# Led_Strip_2_colors.net
KiCad netlist of a schematic drawn in Altium Designer
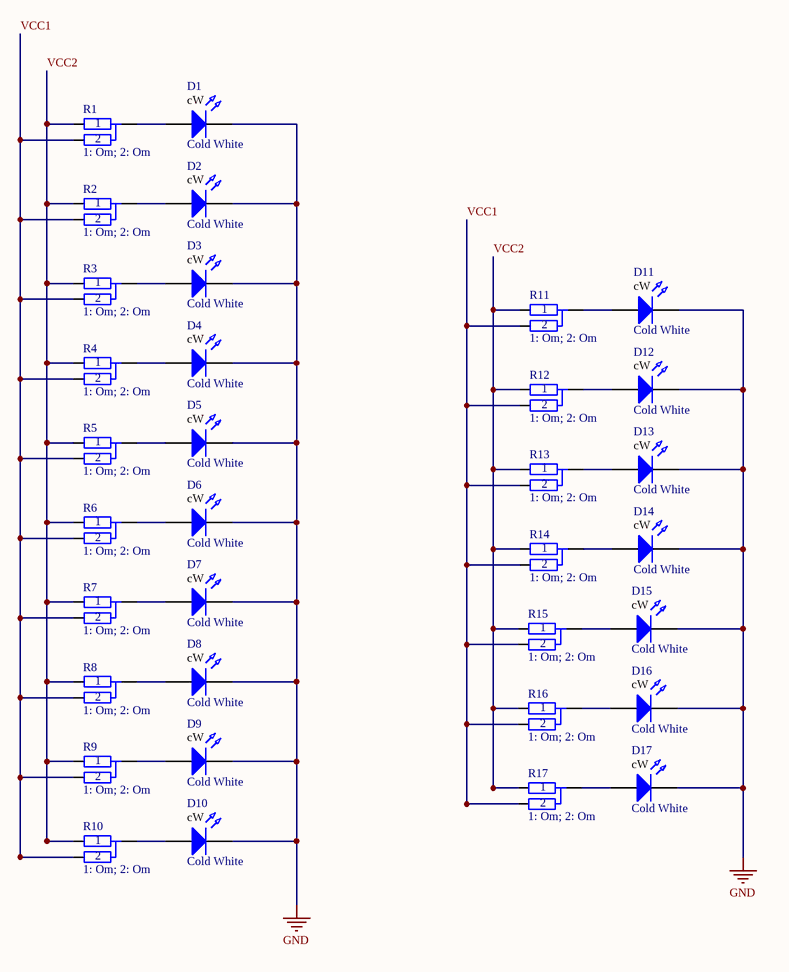
[diagram p0: Led Strip 2 colors.SchDoc]

(export (version "E")
  (design (tool "Eeschema 10.0.6"))
  (components
    (comp (ref "D1")
      (value "Cold White")
      (footprint "LED:LED SMD 5050 White compact R")
      (description "?3v ?20mA")
      (libsource (lib "LED") (part "Led SMD White Cold"))
    )
    (comp (ref "D2")
      (value "Cold White")
      (footprint "LED:LED SMD 5050 White compact R")
      (description "?3v ?20mA")
      (libsource (lib "LED") (part "Led SMD White Cold"))
    )
    (comp (ref "D3")
      (value "Cold White")
      (footprint "LED:LED SMD 5050 White compact R")
      (description "?3v ?20mA")
      (libsource (lib "LED") (part "Led SMD White Cold"))
    )
    (comp (ref "D4")
      (value "Cold White")
      (footprint "LED:LED SMD 5050 White compact R")
      (description "?3v ?20mA")
      (libsource (lib "LED") (part "Led SMD White Cold"))
    )
    (comp (ref "D5")
      (value "Cold White")
      (footprint "LED:LED SMD 5050 White compact R")
      (description "?3v ?20mA")
      (libsource (lib "LED") (part "Led SMD White Cold"))
    )
    (comp (ref "D6")
      (value "Cold White")
      (footprint "LED:LED SMD 5050 White compact R")
      (description "?3v ?20mA")
      (libsource (lib "LED") (part "Led SMD White Cold"))
    )
    (comp (ref "D7")
      (value "Cold White")
      (footprint "LED:LED SMD 5050 White compact R")
      (description "?3v ?20mA")
      (libsource (lib "LED") (part "Led SMD White Cold"))
    )
    (comp (ref "D8")
      (value "Cold White")
      (footprint "LED:LED SMD 5050 White compact R")
      (description "?3v ?20mA")
      (libsource (lib "LED") (part "Led SMD White Cold"))
    )
    (comp (ref "D9")
      (value "Cold White")
      (footprint "LED:LED SMD 5050 White compact R")
      (description "?3v ?20mA")
      (libsource (lib "LED") (part "Led SMD White Cold"))
    )
    (comp (ref "D10")
      (value "Cold White")
      (footprint "LED:LED SMD 5050 White compact R")
      (description "?3v ?20mA")
      (libsource (lib "LED") (part "Led SMD White Cold"))
    )
    (comp (ref "D11")
      (value "Cold White")
      (footprint "LED:LED SMD 5050 White compact R")
      (description "?3v ?20mA")
      (libsource (lib "LED") (part "Led SMD White Cold"))
    )
    (comp (ref "D12")
      (value "Cold White")
      (footprint "LED:LED SMD 5050 White compact R")
      (description "?3v ?20mA")
      (libsource (lib "LED") (part "Led SMD White Cold"))
    )
    (comp (ref "D13")
      (value "Cold White")
      (footprint "LED:LED SMD 5050 White compact R")
      (description "?3v ?20mA")
      (libsource (lib "LED") (part "Led SMD White Cold"))
    )
    (comp (ref "D14")
      (value "Cold White")
      (footprint "LED:LED SMD 5050 White compact R")
      (description "?3v ?20mA")
      (libsource (lib "LED") (part "Led SMD White Cold"))
    )
    (comp (ref "D15")
      (value "Cold White")
      (footprint "LED:LED SMD 5050 White compact R")
      (description "?3v ?20mA")
      (libsource (lib "LED") (part "Led SMD White Cold"))
    )
    (comp (ref "D16")
      (value "Cold White")
      (footprint "LED:LED SMD 5050 White compact R")
      (description "?3v ?20mA")
      (libsource (lib "LED") (part "Led SMD White Cold"))
    )
    (comp (ref "D17")
      (value "Cold White")
      (footprint "LED:LED SMD 5050 White compact R")
      (description "?3v ?20mA")
      (libsource (lib "LED") (part "Led SMD White Cold"))
    )
    (comp (ref "R1")
      (value "1: Om; 2: Om")
      (footprint "PassiveComponents:SMD 0805 (2012) Double")
      (description "Choice from two resistors")
      (libsource (lib "PassiveComponents") (part "Res SMD (Select one way)"))
    )
    (comp (ref "R2")
      (value "1: Om; 2: Om")
      (footprint "PassiveComponents:SMD 0805 (2012) Double")
      (description "Choice from two resistors")
      (libsource (lib "PassiveComponents") (part "Res SMD (Select one way)"))
    )
    (comp (ref "R3")
      (value "1: Om; 2: Om")
      (footprint "PassiveComponents:SMD 0805 (2012) Double")
      (description "Choice from two resistors")
      (libsource (lib "PassiveComponents") (part "Res SMD (Select one way)"))
    )
    (comp (ref "R4")
      (value "1: Om; 2: Om")
      (footprint "PassiveComponents:SMD 0805 (2012) Double")
      (description "Choice from two resistors")
      (libsource (lib "PassiveComponents") (part "Res SMD (Select one way)"))
    )
    (comp (ref "R5")
      (value "1: Om; 2: Om")
      (footprint "PassiveComponents:SMD 0805 (2012) Double")
      (description "Choice from two resistors")
      (libsource (lib "PassiveComponents") (part "Res SMD (Select one way)"))
    )
    (comp (ref "R6")
      (value "1: Om; 2: Om")
      (footprint "PassiveComponents:SMD 0805 (2012) Double")
      (description "Choice from two resistors")
      (libsource (lib "PassiveComponents") (part "Res SMD (Select one way)"))
    )
    (comp (ref "R7")
      (value "1: Om; 2: Om")
      (footprint "PassiveComponents:SMD 0805 (2012) Double")
      (description "Choice from two resistors")
      (libsource (lib "PassiveComponents") (part "Res SMD (Select one way)"))
    )
    (comp (ref "R8")
      (value "1: Om; 2: Om")
      (footprint "PassiveComponents:SMD 0805 (2012) Double")
      (description "Choice from two resistors")
      (libsource (lib "PassiveComponents") (part "Res SMD (Select one way)"))
    )
    (comp (ref "R9")
      (value "1: Om; 2: Om")
      (footprint "PassiveComponents:SMD 0805 (2012) Double")
      (description "Choice from two resistors")
      (libsource (lib "PassiveComponents") (part "Res SMD (Select one way)"))
    )
    (comp (ref "R10")
      (value "1: Om; 2: Om")
      (footprint "PassiveComponents:SMD 0805 (2012) Double")
      (description "Choice from two resistors")
      (libsource (lib "PassiveComponents") (part "Res SMD (Select one way)"))
    )
    (comp (ref "R11")
      (value "1: Om; 2: Om")
      (footprint "PassiveComponents:SMD 0805 (2012) Double")
      (description "Choice from two resistors")
      (libsource (lib "PassiveComponents") (part "Res SMD (Select one way)"))
    )
    (comp (ref "R12")
      (value "1: Om; 2: Om")
      (footprint "PassiveComponents:SMD 0805 (2012) Double")
      (description "Choice from two resistors")
      (libsource (lib "PassiveComponents") (part "Res SMD (Select one way)"))
    )
    (comp (ref "R13")
      (value "1: Om; 2: Om")
      (footprint "PassiveComponents:SMD 0805 (2012) Double")
      (description "Choice from two resistors")
      (libsource (lib "PassiveComponents") (part "Res SMD (Select one way)"))
    )
    (comp (ref "R14")
      (value "1: Om; 2: Om")
      (footprint "PassiveComponents:SMD 0805 (2012) Double")
      (description "Choice from two resistors")
      (libsource (lib "PassiveComponents") (part "Res SMD (Select one way)"))
    )
    (comp (ref "R15")
      (value "1: Om; 2: Om")
      (footprint "PassiveComponents:SMD 0805 (2012) Double")
      (description "Choice from two resistors")
      (libsource (lib "PassiveComponents") (part "Res SMD (Select one way)"))
    )
    (comp (ref "R16")
      (value "1: Om; 2: Om")
      (footprint "PassiveComponents:SMD 0805 (2012) Double")
      (description "Choice from two resistors")
      (libsource (lib "PassiveComponents") (part "Res SMD (Select one way)"))
    )
    (comp (ref "R17")
      (value "1: Om; 2: Om")
      (footprint "PassiveComponents:SMD 0805 (2012) Double")
      (description "Choice from two resistors")
      (libsource (lib "PassiveComponents") (part "Res SMD (Select one way)"))
    )
  )
  (nets
    (net (code "1") (name "/VCC1") (class "Default")
      (node (ref "R1") (pin "2") (pinfunction "2_2") (pintype "passive"))
      (node (ref "R10") (pin "2") (pinfunction "2_2") (pintype "passive"))
      (node (ref "R11") (pin "2") (pinfunction "2_2") (pintype "passive"))
      (node (ref "R12") (pin "2") (pinfunction "2_2") (pintype "passive"))
      (node (ref "R13") (pin "2") (pinfunction "2_2") (pintype "passive"))
      (node (ref "R14") (pin "2") (pinfunction "2_2") (pintype "passive"))
      (node (ref "R15") (pin "2") (pinfunction "2_2") (pintype "passive"))
      (node (ref "R16") (pin "2") (pinfunction "2_2") (pintype "passive"))
      (node (ref "R17") (pin "2") (pinfunction "2_2") (pintype "passive"))
      (node (ref "R2") (pin "2") (pinfunction "2_2") (pintype "passive"))
      (node (ref "R3") (pin "2") (pinfunction "2_2") (pintype "passive"))
      (node (ref "R4") (pin "2") (pinfunction "2_2") (pintype "passive"))
      (node (ref "R5") (pin "2") (pinfunction "2_2") (pintype "passive"))
      (node (ref "R6") (pin "2") (pinfunction "2_2") (pintype "passive"))
      (node (ref "R7") (pin "2") (pinfunction "2_2") (pintype "passive"))
      (node (ref "R8") (pin "2") (pinfunction "2_2") (pintype "passive"))
      (node (ref "R9") (pin "2") (pinfunction "2_2") (pintype "passive"))
    )
    (net (code "2") (name "/VCC2") (class "Default")
      (node (ref "R1") (pin "1") (pinfunction "1_1") (pintype "passive"))
      (node (ref "R10") (pin "1") (pinfunction "1_1") (pintype "passive"))
      (node (ref "R11") (pin "1") (pinfunction "1_1") (pintype "passive"))
      (node (ref "R12") (pin "1") (pinfunction "1_1") (pintype "passive"))
      (node (ref "R13") (pin "1") (pinfunction "1_1") (pintype "passive"))
      (node (ref "R14") (pin "1") (pinfunction "1_1") (pintype "passive"))
      (node (ref "R15") (pin "1") (pinfunction "1_1") (pintype "passive"))
      (node (ref "R16") (pin "1") (pinfunction "1_1") (pintype "passive"))
      (node (ref "R17") (pin "1") (pinfunction "1_1") (pintype "passive"))
      (node (ref "R2") (pin "1") (pinfunction "1_1") (pintype "passive"))
      (node (ref "R3") (pin "1") (pinfunction "1_1") (pintype "passive"))
      (node (ref "R4") (pin "1") (pinfunction "1_1") (pintype "passive"))
      (node (ref "R5") (pin "1") (pinfunction "1_1") (pintype "passive"))
      (node (ref "R6") (pin "1") (pinfunction "1_1") (pintype "passive"))
      (node (ref "R7") (pin "1") (pinfunction "1_1") (pintype "passive"))
      (node (ref "R8") (pin "1") (pinfunction "1_1") (pintype "passive"))
      (node (ref "R9") (pin "1") (pinfunction "1_1") (pintype "passive"))
    )
    (net (code "3") (name "GND") (class "Default")
      (node (ref "D1") (pin "K") (pinfunction "K_K") (pintype "passive"))
      (node (ref "D10") (pin "K") (pinfunction "K_K") (pintype "passive"))
      (node (ref "D11") (pin "K") (pinfunction "K_K") (pintype "passive"))
      (node (ref "D12") (pin "K") (pinfunction "K_K") (pintype "passive"))
      (node (ref "D13") (pin "K") (pinfunction "K_K") (pintype "passive"))
      (node (ref "D14") (pin "K") (pinfunction "K_K") (pintype "passive"))
      (node (ref "D15") (pin "K") (pinfunction "K_K") (pintype "passive"))
      (node (ref "D16") (pin "K") (pinfunction "K_K") (pintype "passive"))
      (node (ref "D17") (pin "K") (pinfunction "K_K") (pintype "passive"))
      (node (ref "D2") (pin "K") (pinfunction "K_K") (pintype "passive"))
      (node (ref "D3") (pin "K") (pinfunction "K_K") (pintype "passive"))
      (node (ref "D4") (pin "K") (pinfunction "K_K") (pintype "passive"))
      (node (ref "D5") (pin "K") (pinfunction "K_K") (pintype "passive"))
      (node (ref "D6") (pin "K") (pinfunction "K_K") (pintype "passive"))
      (node (ref "D7") (pin "K") (pinfunction "K_K") (pintype "passive"))
      (node (ref "D8") (pin "K") (pinfunction "K_K") (pintype "passive"))
      (node (ref "D9") (pin "K") (pinfunction "K_K") (pintype "passive"))
    )
    (net (code "4") (name "Net-(D1-PadA)") (class "Default")
      (node (ref "D1") (pin "A") (pinfunction "A_A") (pintype "passive"))
      (node (ref "R1") (pin "3") (pinfunction "3_3") (pintype "passive"))
    )
    (net (code "5") (name "Net-(D2-PadA)") (class "Default")
      (node (ref "D2") (pin "A") (pinfunction "A_A") (pintype "passive"))
      (node (ref "R2") (pin "3") (pinfunction "3_3") (pintype "passive"))
    )
    (net (code "6") (name "Net-(D3-PadA)") (class "Default")
      (node (ref "D3") (pin "A") (pinfunction "A_A") (pintype "passive"))
      (node (ref "R3") (pin "3") (pinfunction "3_3") (pintype "passive"))
    )
    (net (code "7") (name "Net-(D4-PadA)") (class "Default")
      (node (ref "D4") (pin "A") (pinfunction "A_A") (pintype "passive"))
      (node (ref "R4") (pin "3") (pinfunction "3_3") (pintype "passive"))
    )
    (net (code "8") (name "Net-(D5-PadA)") (class "Default")
      (node (ref "D5") (pin "A") (pinfunction "A_A") (pintype "passive"))
      (node (ref "R5") (pin "3") (pinfunction "3_3") (pintype "passive"))
    )
    (net (code "9") (name "Net-(D6-PadA)") (class "Default")
      (node (ref "D6") (pin "A") (pinfunction "A_A") (pintype "passive"))
      (node (ref "R6") (pin "3") (pinfunction "3_3") (pintype "passive"))
    )
    (net (code "10") (name "Net-(D7-PadA)") (class "Default")
      (node (ref "D7") (pin "A") (pinfunction "A_A") (pintype "passive"))
      (node (ref "R7") (pin "3") (pinfunction "3_3") (pintype "passive"))
    )
    (net (code "11") (name "Net-(D8-PadA)") (class "Default")
      (node (ref "D8") (pin "A") (pinfunction "A_A") (pintype "passive"))
      (node (ref "R8") (pin "3") (pinfunction "3_3") (pintype "passive"))
    )
    (net (code "12") (name "Net-(D9-PadA)") (class "Default")
      (node (ref "D9") (pin "A") (pinfunction "A_A") (pintype "passive"))
      (node (ref "R9") (pin "3") (pinfunction "3_3") (pintype "passive"))
    )
    (net (code "13") (name "Net-(D10-PadA)") (class "Default")
      (node (ref "D10") (pin "A") (pinfunction "A_A") (pintype "passive"))
      (node (ref "R10") (pin "3") (pinfunction "3_3") (pintype "passive"))
    )
    (net (code "14") (name "Net-(D11-PadA)") (class "Default")
      (node (ref "D11") (pin "A") (pinfunction "A_A") (pintype "passive"))
      (node (ref "R11") (pin "3") (pinfunction "3_3") (pintype "passive"))
    )
    (net (code "15") (name "Net-(D12-PadA)") (class "Default")
      (node (ref "D12") (pin "A") (pinfunction "A_A") (pintype "passive"))
      (node (ref "R12") (pin "3") (pinfunction "3_3") (pintype "passive"))
    )
    (net (code "16") (name "Net-(D13-PadA)") (class "Default")
      (node (ref "D13") (pin "A") (pinfunction "A_A") (pintype "passive"))
      (node (ref "R13") (pin "3") (pinfunction "3_3") (pintype "passive"))
    )
    (net (code "17") (name "Net-(D14-PadA)") (class "Default")
      (node (ref "D14") (pin "A") (pinfunction "A_A") (pintype "passive"))
      (node (ref "R14") (pin "3") (pinfunction "3_3") (pintype "passive"))
    )
    (net (code "18") (name "Net-(D15-PadA)") (class "Default")
      (node (ref "D15") (pin "A") (pinfunction "A_A") (pintype "passive"))
      (node (ref "R15") (pin "3") (pinfunction "3_3") (pintype "passive"))
    )
    (net (code "19") (name "Net-(D16-PadA)") (class "Default")
      (node (ref "D16") (pin "A") (pinfunction "A_A") (pintype "passive"))
      (node (ref "R16") (pin "3") (pinfunction "3_3") (pintype "passive"))
    )
    (net (code "20") (name "Net-(D17-PadA)") (class "Default")
      (node (ref "D17") (pin "A") (pinfunction "A_A") (pintype "passive"))
      (node (ref "R17") (pin "3") (pinfunction "3_3") (pintype "passive"))
    )
  )
)
